# JTAG.net
KiCad netlist of a schematic drawn in Altium Designer
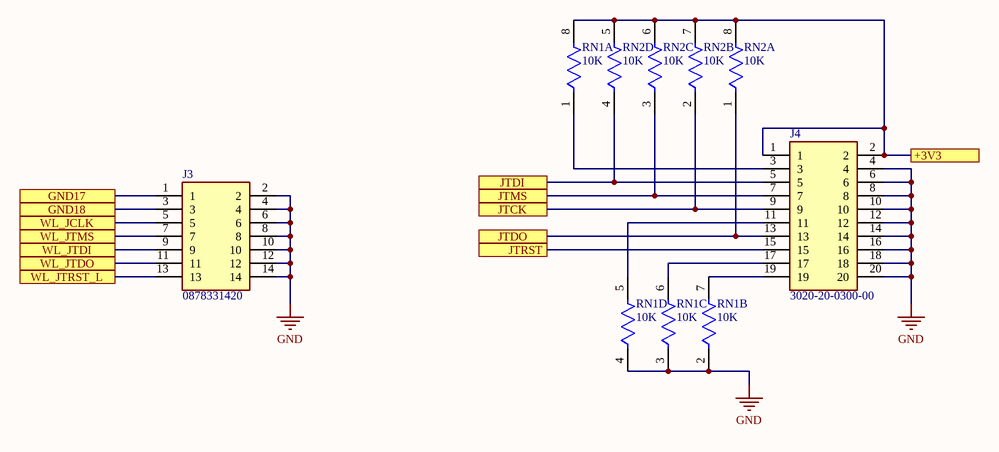
[diagram p0: JTAG.SchDoc]

(export (version "E")
  (design (tool "Eeschema 10.0.6"))
  (components
    (comp (ref "J3")
      (value "0878331420")
      (footprint "SamacSys:SHDRRA14W55P200_2X7_1665X640X630P")
      (description "Connector")
      (libsource (lib "*") (part "0878331420"))
    )
    (comp (ref "J4")
      (value "3020-20-0300-00")
      (footprint "SamacSys:302020030000")
      (description "Connector")
      (libsource (lib "*") (part "3020-20-0300-00"))
    )
    (comp (ref "RN1")
      (value "10K")
      (footprint "FP-CAT16-F4-MFG")
      (description "RES ARRAY 4 RES 10K OHM 1206")
      (fields (field (name "MANUFACTURER PART NUMBER") "CAT16-1002F4LF") (field (name "TOLERANCE") "1%"))
      (libsource (lib "Altium Content Vault") (part "46c0e806a6f3a765a2d55930d12d044"))
    )
    (comp (ref "RN2")
      (value "10K")
      (footprint "FP-CAT16-F4-MFG")
      (description "RES ARRAY 4 RES 10K OHM 1206")
      (fields (field (name "MANUFACTURER PART NUMBER") "CAT16-1002F4LF") (field (name "TOLERANCE") "1%"))
      (libsource (lib "Altium Content Vault") (part "46c0e806a6f3a765a2d55930d12d044"))
    )
  )
  (nets
    (net (code "1") (name "/+3V3") (class "Default")
      (node (ref "J4") (pin "1") (pinfunction "1_1") (pintype "passive"))
      (node (ref "J4") (pin "2") (pinfunction "2_2") (pintype "passive"))
      (node (ref "RN1") (pin "8") (pinfunction "8_8") (pintype "passive"))
      (node (ref "RN2") (pin "5") (pinfunction "5_5") (pintype "passive"))
      (node (ref "RN2") (pin "6") (pinfunction "6_6") (pintype "passive"))
      (node (ref "RN2") (pin "7") (pinfunction "7_7") (pintype "passive"))
      (node (ref "RN2") (pin "8") (pinfunction "8_8") (pintype "passive"))
    )
    (net (code "2") (name "/GND17") (class "Default")
      (node (ref "J3") (pin "1") (pinfunction "1_1") (pintype "passive"))
    )
    (net (code "3") (name "/GND18") (class "Default")
      (node (ref "J3") (pin "3") (pinfunction "3_3") (pintype "passive"))
    )
    (net (code "4") (name "/JTCK") (class "Default")
      (node (ref "J4") (pin "9") (pinfunction "9_9") (pintype "passive"))
      (node (ref "RN2") (pin "2") (pinfunction "2_2") (pintype "passive"))
    )
    (net (code "5") (name "/JTDI") (class "Default")
      (node (ref "J4") (pin "5") (pinfunction "5_5") (pintype "passive"))
      (node (ref "RN2") (pin "4") (pinfunction "4_4") (pintype "passive"))
    )
    (net (code "6") (name "/JTDO") (class "Default")
      (node (ref "J4") (pin "13") (pinfunction "13_13") (pintype "passive"))
      (node (ref "RN2") (pin "1") (pinfunction "1_1") (pintype "passive"))
    )
    (net (code "7") (name "/JTMS") (class "Default")
      (node (ref "J4") (pin "7") (pinfunction "7_7") (pintype "passive"))
      (node (ref "RN2") (pin "3") (pinfunction "3_3") (pintype "passive"))
    )
    (net (code "8") (name "/JTRST") (class "Default")
      (node (ref "J4") (pin "15") (pinfunction "15_15") (pintype "passive"))
    )
    (net (code "9") (name "/WL_JCLK") (class "Default")
      (node (ref "J3") (pin "5") (pinfunction "5_5") (pintype "passive"))
    )
    (net (code "10") (name "/WL_JTDI") (class "Default")
      (node (ref "J3") (pin "9") (pinfunction "9_9") (pintype "passive"))
    )
    (net (code "11") (name "/WL_JTDO") (class "Default")
      (node (ref "J3") (pin "11") (pinfunction "11_11") (pintype "passive"))
    )
    (net (code "12") (name "/WL_JTMS") (class "Default")
      (node (ref "J3") (pin "7") (pinfunction "7_7") (pintype "passive"))
    )
    (net (code "13") (name "/WL_JTRST_L") (class "Default")
      (node (ref "J3") (pin "13") (pinfunction "13_13") (pintype "passive"))
    )
    (net (code "14") (name "GND") (class "Default")
      (node (ref "J3") (pin "10") (pinfunction "10_10") (pintype "passive"))
      (node (ref "J3") (pin "12") (pinfunction "12_12") (pintype "passive"))
      (node (ref "J3") (pin "14") (pinfunction "14_14") (pintype "passive"))
      (node (ref "J3") (pin "2") (pinfunction "2_2") (pintype "passive"))
      (node (ref "J3") (pin "4") (pinfunction "4_4") (pintype "passive"))
      (node (ref "J3") (pin "6") (pinfunction "6_6") (pintype "passive"))
      (node (ref "J3") (pin "8") (pinfunction "8_8") (pintype "passive"))
      (node (ref "J4") (pin "10") (pinfunction "10_10") (pintype "passive"))
      (node (ref "J4") (pin "12") (pinfunction "12_12") (pintype "passive"))
      (node (ref "J4") (pin "14") (pinfunction "14_14") (pintype "passive"))
      (node (ref "J4") (pin "16") (pinfunction "16_16") (pintype "passive"))
      (node (ref "J4") (pin "18") (pinfunction "18_18") (pintype "passive"))
      (node (ref "J4") (pin "20") (pinfunction "20_20") (pintype "passive"))
      (node (ref "J4") (pin "4") (pinfunction "4_4") (pintype "passive"))
      (node (ref "J4") (pin "6") (pinfunction "6_6") (pintype "passive"))
      (node (ref "J4") (pin "8") (pinfunction "8_8") (pintype "passive"))
      (node (ref "RN1") (pin "2") (pinfunction "2_2") (pintype "passive"))
      (node (ref "RN1") (pin "3") (pinfunction "3_3") (pintype "passive"))
      (node (ref "RN1") (pin "4") (pinfunction "4_4") (pintype "passive"))
    )
    (net (code "15") (name "Net-(J4-Pad3)") (class "Default")
      (node (ref "J4") (pin "3") (pinfunction "3_3") (pintype "passive"))
      (node (ref "RN1") (pin "1") (pinfunction "1_1") (pintype "passive"))
    )
    (net (code "16") (name "Net-(J4-Pad11)") (class "Default")
      (node (ref "J4") (pin "11") (pinfunction "11_11") (pintype "passive"))
      (node (ref "RN1") (pin "5") (pinfunction "5_5") (pintype "passive"))
    )
    (net (code "17") (name "Net-(J4-Pad17)") (class "Default")
      (node (ref "J4") (pin "17") (pinfunction "17_17") (pintype "passive"))
      (node (ref "RN1") (pin "6") (pinfunction "6_6") (pintype "passive"))
    )
    (net (code "18") (name "Net-(J4-Pad19)") (class "Default")
      (node (ref "J4") (pin "19") (pinfunction "19_19") (pintype "passive"))
      (node (ref "RN1") (pin "7") (pinfunction "7_7") (pintype "passive"))
    )
  )
)
